# Exercise1.net
KiCad netlist of a schematic drawn in EAGLE
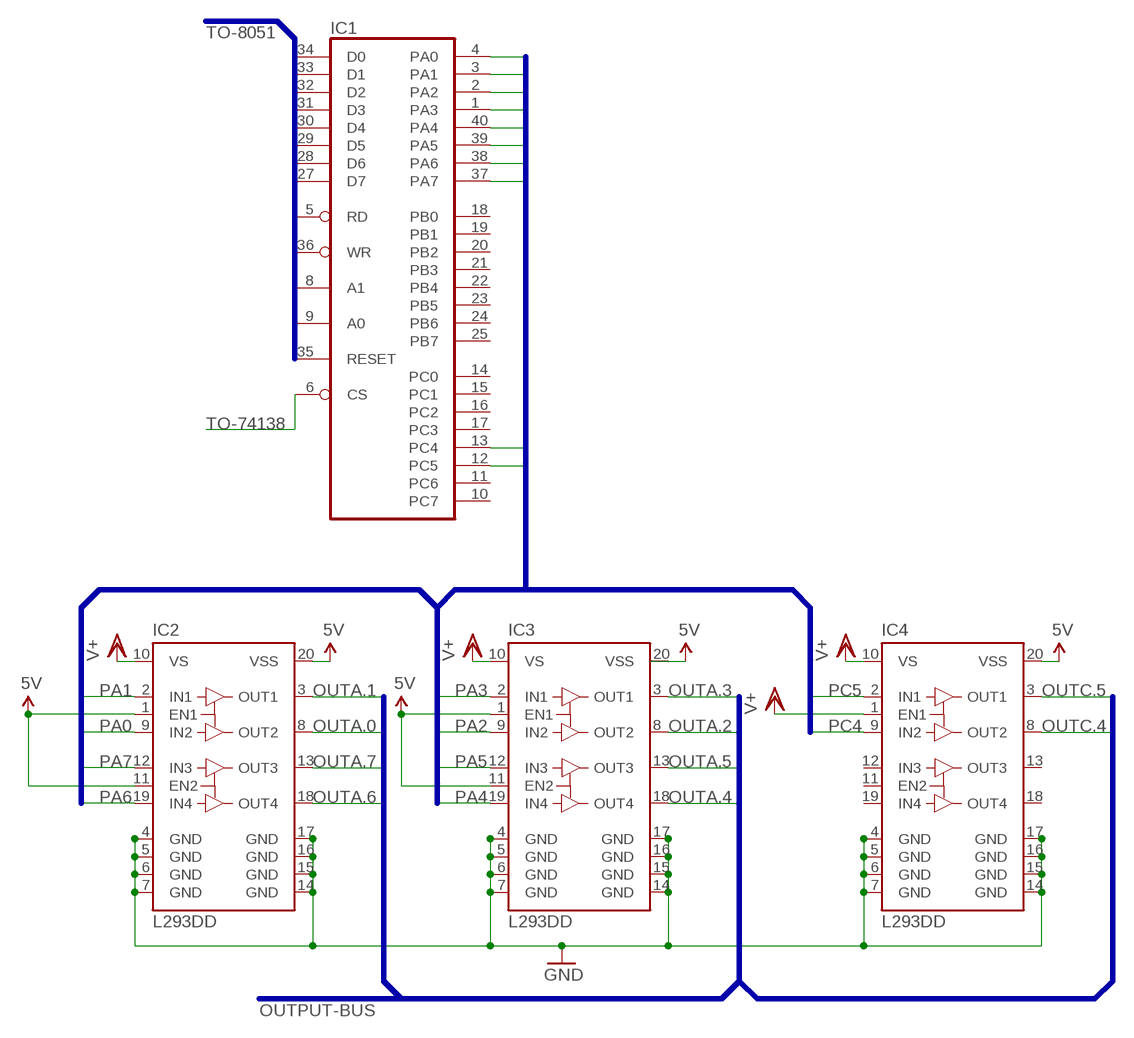
[diagram p0: schematic, sheet 1]

(export (version "E")
  (design (tool "Eeschema 10.0.6"))
  (components
    (comp (ref "IC1")
      (value "8255A")
      (footprint "eagle-import:DIL40")
      (libsource (lib "eagle-import") (part "8255A"))
    )
    (comp (ref "IC2")
      (value "L293DD")
      (footprint "eagle-import:SO20")
      (libsource (lib "eagle-import") (part "L293DD"))
    )
    (comp (ref "IC3")
      (value "L293DD")
      (footprint "eagle-import:SO20")
      (libsource (lib "eagle-import") (part "L293DD"))
    )
    (comp (ref "IC4")
      (value "L293DD")
      (footprint "eagle-import:SO20")
      (libsource (lib "eagle-import") (part "L293DD"))
    )
  )
  (nets
    (net (code "3") (name "/N$1") (class "Default")
      (node (ref "IC1") (pin "1") (pinfunction "PA3_1") (pintype "bidirectional"))
      (node (ref "IC1") (pin "12") (pinfunction "PC5_12") (pintype "bidirectional"))
      (node (ref "IC1") (pin "13") (pinfunction "PC4_13") (pintype "bidirectional"))
      (node (ref "IC1") (pin "2") (pinfunction "PA2_2") (pintype "bidirectional"))
      (node (ref "IC1") (pin "3") (pinfunction "PA1_3") (pintype "bidirectional"))
      (node (ref "IC1") (pin "37") (pinfunction "PA7_37") (pintype "bidirectional"))
      (node (ref "IC1") (pin "38") (pinfunction "PA6_38") (pintype "bidirectional"))
      (node (ref "IC1") (pin "39") (pinfunction "PA5_39") (pintype "bidirectional"))
      (node (ref "IC1") (pin "4") (pinfunction "PA0_4") (pintype "bidirectional"))
      (node (ref "IC1") (pin "40") (pinfunction "PA4_40") (pintype "bidirectional"))
    )
    (net (code "4") (name "/OUTA.0") (class "Default")
      (node (ref "IC2") (pin "8") (pinfunction "OUT2_8") (pintype "output"))
    )
    (net (code "5") (name "/OUTA.1") (class "Default")
      (node (ref "IC2") (pin "3") (pinfunction "OUT1_3") (pintype "output"))
    )
    (net (code "6") (name "/OUTA.2") (class "Default")
      (node (ref "IC3") (pin "8") (pinfunction "OUT2_8") (pintype "output"))
    )
    (net (code "7") (name "/OUTA.3") (class "Default")
      (node (ref "IC3") (pin "3") (pinfunction "OUT1_3") (pintype "output"))
    )
    (net (code "8") (name "/OUTA.4") (class "Default")
      (node (ref "IC3") (pin "18") (pinfunction "OUT4_18") (pintype "output"))
    )
    (net (code "9") (name "/OUTA.5") (class "Default")
      (node (ref "IC3") (pin "13") (pinfunction "OUT3_13") (pintype "output"))
    )
    (net (code "10") (name "/OUTA.6") (class "Default")
      (node (ref "IC2") (pin "18") (pinfunction "OUT4_18") (pintype "output"))
    )
    (net (code "11") (name "/OUTA.7") (class "Default")
      (node (ref "IC2") (pin "13") (pinfunction "OUT3_13") (pintype "output"))
    )
    (net (code "12") (name "/OUTC.4") (class "Default")
      (node (ref "IC4") (pin "8") (pinfunction "OUT2_8") (pintype "output"))
    )
    (net (code "13") (name "/OUTC.5") (class "Default")
      (node (ref "IC4") (pin "3") (pinfunction "OUT1_3") (pintype "output"))
    )
    (net (code "14") (name "/PA0") (class "Default")
      (node (ref "IC2") (pin "9") (pinfunction "IN2_9") (pintype "input"))
    )
    (net (code "15") (name "/PA1") (class "Default")
      (node (ref "IC2") (pin "2") (pinfunction "IN1_2") (pintype "input"))
    )
    (net (code "16") (name "/PA2") (class "Default")
      (node (ref "IC3") (pin "9") (pinfunction "IN2_9") (pintype "input"))
    )
    (net (code "17") (name "/PA3") (class "Default")
      (node (ref "IC3") (pin "2") (pinfunction "IN1_2") (pintype "input"))
    )
    (net (code "18") (name "/PA4") (class "Default")
      (node (ref "IC3") (pin "19") (pinfunction "IN4_19") (pintype "input"))
    )
    (net (code "19") (name "/PA5") (class "Default")
      (node (ref "IC3") (pin "12") (pinfunction "IN3_12") (pintype "input"))
    )
    (net (code "20") (name "/PA6") (class "Default")
      (node (ref "IC2") (pin "19") (pinfunction "IN4_19") (pintype "input"))
    )
    (net (code "21") (name "/PA7") (class "Default")
      (node (ref "IC2") (pin "12") (pinfunction "IN3_12") (pintype "input"))
    )
    (net (code "22") (name "/PC4") (class "Default")
      (node (ref "IC4") (pin "9") (pinfunction "IN2_9") (pintype "input"))
    )
    (net (code "23") (name "/PC5") (class "Default")
      (node (ref "IC4") (pin "2") (pinfunction "IN1_2") (pintype "input"))
    )
    (net (code "24") (name "/TO-74138") (class "Default")
      (node (ref "IC1") (pin "6") (pinfunction "CS_6") (pintype "input"))
    )
    (net (code "26") (name "/{TO-8051}") (class "Default")
      (node (ref "IC1") (pin "35") (pinfunction "RESET_35") (pintype "input"))
    )
    (net (code "27") (name "5V") (class "Default")
      (node (ref "IC2") (pin "1") (pinfunction "EN1_1") (pintype "input"))
      (node (ref "IC2") (pin "11") (pinfunction "EN2_11") (pintype "input"))
      (node (ref "IC2") (pin "20") (pinfunction "VSS_20") (pintype "power_in"))
      (node (ref "IC3") (pin "1") (pinfunction "EN1_1") (pintype "input"))
      (node (ref "IC3") (pin "11") (pinfunction "EN2_11") (pintype "input"))
      (node (ref "IC3") (pin "20") (pinfunction "VSS_20") (pintype "power_in"))
      (node (ref "IC4") (pin "20") (pinfunction "VSS_20") (pintype "power_in"))
    )
    (net (code "28") (name "GND") (class "Default")
      (node (ref "IC2") (pin "14") (pinfunction "GND_14") (pintype "power_in"))
      (node (ref "IC2") (pin "15") (pinfunction "GND_15") (pintype "power_in"))
      (node (ref "IC2") (pin "16") (pinfunction "GND_16") (pintype "power_in"))
      (node (ref "IC2") (pin "17") (pinfunction "GND_17") (pintype "power_in"))
      (node (ref "IC2") (pin "4") (pinfunction "GND_4") (pintype "power_in"))
      (node (ref "IC2") (pin "5") (pinfunction "GND_5") (pintype "power_in"))
      (node (ref "IC2") (pin "6") (pinfunction "GND_6") (pintype "power_in"))
      (node (ref "IC2") (pin "7") (pinfunction "GND_7") (pintype "power_in"))
      (node (ref "IC3") (pin "14") (pinfunction "GND_14") (pintype "power_in"))
      (node (ref "IC3") (pin "15") (pinfunction "GND_15") (pintype "power_in"))
      (node (ref "IC3") (pin "16") (pinfunction "GND_16") (pintype "power_in"))
      (node (ref "IC3") (pin "17") (pinfunction "GND_17") (pintype "power_in"))
      (node (ref "IC3") (pin "4") (pinfunction "GND_4") (pintype "power_in"))
      (node (ref "IC3") (pin "5") (pinfunction "GND_5") (pintype "power_in"))
      (node (ref "IC3") (pin "6") (pinfunction "GND_6") (pintype "power_in"))
      (node (ref "IC3") (pin "7") (pinfunction "GND_7") (pintype "power_in"))
      (node (ref "IC4") (pin "14") (pinfunction "GND_14") (pintype "power_in"))
      (node (ref "IC4") (pin "15") (pinfunction "GND_15") (pintype "power_in"))
      (node (ref "IC4") (pin "16") (pinfunction "GND_16") (pintype "power_in"))
      (node (ref "IC4") (pin "17") (pinfunction "GND_17") (pintype "power_in"))
      (node (ref "IC4") (pin "4") (pinfunction "GND_4") (pintype "power_in"))
      (node (ref "IC4") (pin "5") (pinfunction "GND_5") (pintype "power_in"))
      (node (ref "IC4") (pin "6") (pinfunction "GND_6") (pintype "power_in"))
      (node (ref "IC4") (pin "7") (pinfunction "GND_7") (pintype "power_in"))
    )
    (net (code "29") (name "V+") (class "Default")
      (node (ref "IC2") (pin "10") (pinfunction "VS_10") (pintype "power_in"))
      (node (ref "IC3") (pin "10") (pinfunction "VS_10") (pintype "power_in"))
      (node (ref "IC4") (pin "1") (pinfunction "EN1_1") (pintype "input"))
      (node (ref "IC4") (pin "10") (pinfunction "VS_10") (pintype "power_in"))
    )
    (net (code "30") (name "unconnected-(IC1A-A0-Pad9)") (class "Default")
      (node (ref "IC1") (pin "9") (pinfunction "A0_9") (pintype "input"))
    )
    (net (code "31") (name "unconnected-(IC1A-A1-Pad8)") (class "Default")
      (node (ref "IC1") (pin "8") (pinfunction "A1_8") (pintype "input"))
    )
    (net (code "32") (name "unconnected-(IC1A-D0-Pad34)") (class "Default")
      (node (ref "IC1") (pin "34") (pinfunction "D0_34") (pintype "bidirectional"))
    )
    (net (code "33") (name "unconnected-(IC1A-D1-Pad33)") (class "Default")
      (node (ref "IC1") (pin "33") (pinfunction "D1_33") (pintype "bidirectional"))
    )
    (net (code "34") (name "unconnected-(IC1A-D2-Pad32)") (class "Default")
      (node (ref "IC1") (pin "32") (pinfunction "D2_32") (pintype "bidirectional"))
    )
    (net (code "35") (name "unconnected-(IC1A-D3-Pad31)") (class "Default")
      (node (ref "IC1") (pin "31") (pinfunction "D3_31") (pintype "bidirectional"))
    )
    (net (code "36") (name "unconnected-(IC1A-D4-Pad30)") (class "Default")
      (node (ref "IC1") (pin "30") (pinfunction "D4_30") (pintype "bidirectional"))
    )
    (net (code "37") (name "unconnected-(IC1A-D5-Pad29)") (class "Default")
      (node (ref "IC1") (pin "29") (pinfunction "D5_29") (pintype "bidirectional"))
    )
    (net (code "38") (name "unconnected-(IC1A-D6-Pad28)") (class "Default")
      (node (ref "IC1") (pin "28") (pinfunction "D6_28") (pintype "bidirectional"))
    )
    (net (code "39") (name "unconnected-(IC1A-D7-Pad27)") (class "Default")
      (node (ref "IC1") (pin "27") (pinfunction "D7_27") (pintype "bidirectional"))
    )
    (net (code "40") (name "unconnected-(IC1A-PB0-Pad18)") (class "Default")
      (node (ref "IC1") (pin "18") (pinfunction "PB0_18") (pintype "bidirectional"))
    )
    (net (code "41") (name "unconnected-(IC1A-PB1-Pad19)") (class "Default")
      (node (ref "IC1") (pin "19") (pinfunction "PB1_19") (pintype "bidirectional"))
    )
    (net (code "42") (name "unconnected-(IC1A-PB2-Pad20)") (class "Default")
      (node (ref "IC1") (pin "20") (pinfunction "PB2_20") (pintype "bidirectional"))
    )
    (net (code "43") (name "unconnected-(IC1A-PB3-Pad21)") (class "Default")
      (node (ref "IC1") (pin "21") (pinfunction "PB3_21") (pintype "bidirectional"))
    )
    (net (code "44") (name "unconnected-(IC1A-PB4-Pad22)") (class "Default")
      (node (ref "IC1") (pin "22") (pinfunction "PB4_22") (pintype "bidirectional"))
    )
    (net (code "45") (name "unconnected-(IC1A-PB5-Pad23)") (class "Default")
      (node (ref "IC1") (pin "23") (pinfunction "PB5_23") (pintype "bidirectional"))
    )
    (net (code "46") (name "unconnected-(IC1A-PB6-Pad24)") (class "Default")
      (node (ref "IC1") (pin "24") (pinfunction "PB6_24") (pintype "bidirectional"))
    )
    (net (code "47") (name "unconnected-(IC1A-PB7-Pad25)") (class "Default")
      (node (ref "IC1") (pin "25") (pinfunction "PB7_25") (pintype "bidirectional"))
    )
    (net (code "48") (name "unconnected-(IC1A-PC0-Pad14)") (class "Default")
      (node (ref "IC1") (pin "14") (pinfunction "PC0_14") (pintype "bidirectional"))
    )
    (net (code "49") (name "unconnected-(IC1A-PC1-Pad15)") (class "Default")
      (node (ref "IC1") (pin "15") (pinfunction "PC1_15") (pintype "bidirectional"))
    )
    (net (code "50") (name "unconnected-(IC1A-PC2-Pad16)") (class "Default")
      (node (ref "IC1") (pin "16") (pinfunction "PC2_16") (pintype "bidirectional"))
    )
    (net (code "51") (name "unconnected-(IC1A-PC3-Pad17)") (class "Default")
      (node (ref "IC1") (pin "17") (pinfunction "PC3_17") (pintype "bidirectional"))
    )
    (net (code "52") (name "unconnected-(IC1A-PC6-Pad11)") (class "Default")
      (node (ref "IC1") (pin "11") (pinfunction "PC6_11") (pintype "bidirectional"))
    )
    (net (code "53") (name "unconnected-(IC1A-PC7-Pad10)") (class "Default")
      (node (ref "IC1") (pin "10") (pinfunction "PC7_10") (pintype "bidirectional"))
    )
    (net (code "54") (name "unconnected-(IC1A-RD-Pad5)") (class "Default")
      (node (ref "IC1") (pin "5") (pinfunction "RD_5") (pintype "input"))
    )
    (net (code "55") (name "unconnected-(IC1A-WR-Pad36)") (class "Default")
      (node (ref "IC1") (pin "36") (pinfunction "WR_36") (pintype "input"))
    )
    (net (code "56") (name "unconnected-(IC4-EN2-Pad11)") (class "Default")
      (node (ref "IC4") (pin "11") (pinfunction "EN2_11") (pintype "input"))
    )
    (net (code "57") (name "unconnected-(IC4-IN3-Pad12)") (class "Default")
      (node (ref "IC4") (pin "12") (pinfunction "IN3_12") (pintype "input"))
    )
    (net (code "58") (name "unconnected-(IC4-IN4-Pad19)") (class "Default")
      (node (ref "IC4") (pin "19") (pinfunction "IN4_19") (pintype "input"))
    )
    (net (code "59") (name "unconnected-(IC4-OUT3-Pad13)") (class "Default")
      (node (ref "IC4") (pin "13") (pinfunction "OUT3_13") (pintype "output"))
    )
    (net (code "60") (name "unconnected-(IC4-OUT4-Pad18)") (class "Default")
      (node (ref "IC4") (pin "18") (pinfunction "OUT4_18") (pintype "output"))
    )
  )
)
